# SSD.net
KiCad netlist of a schematic drawn in Altium Designer
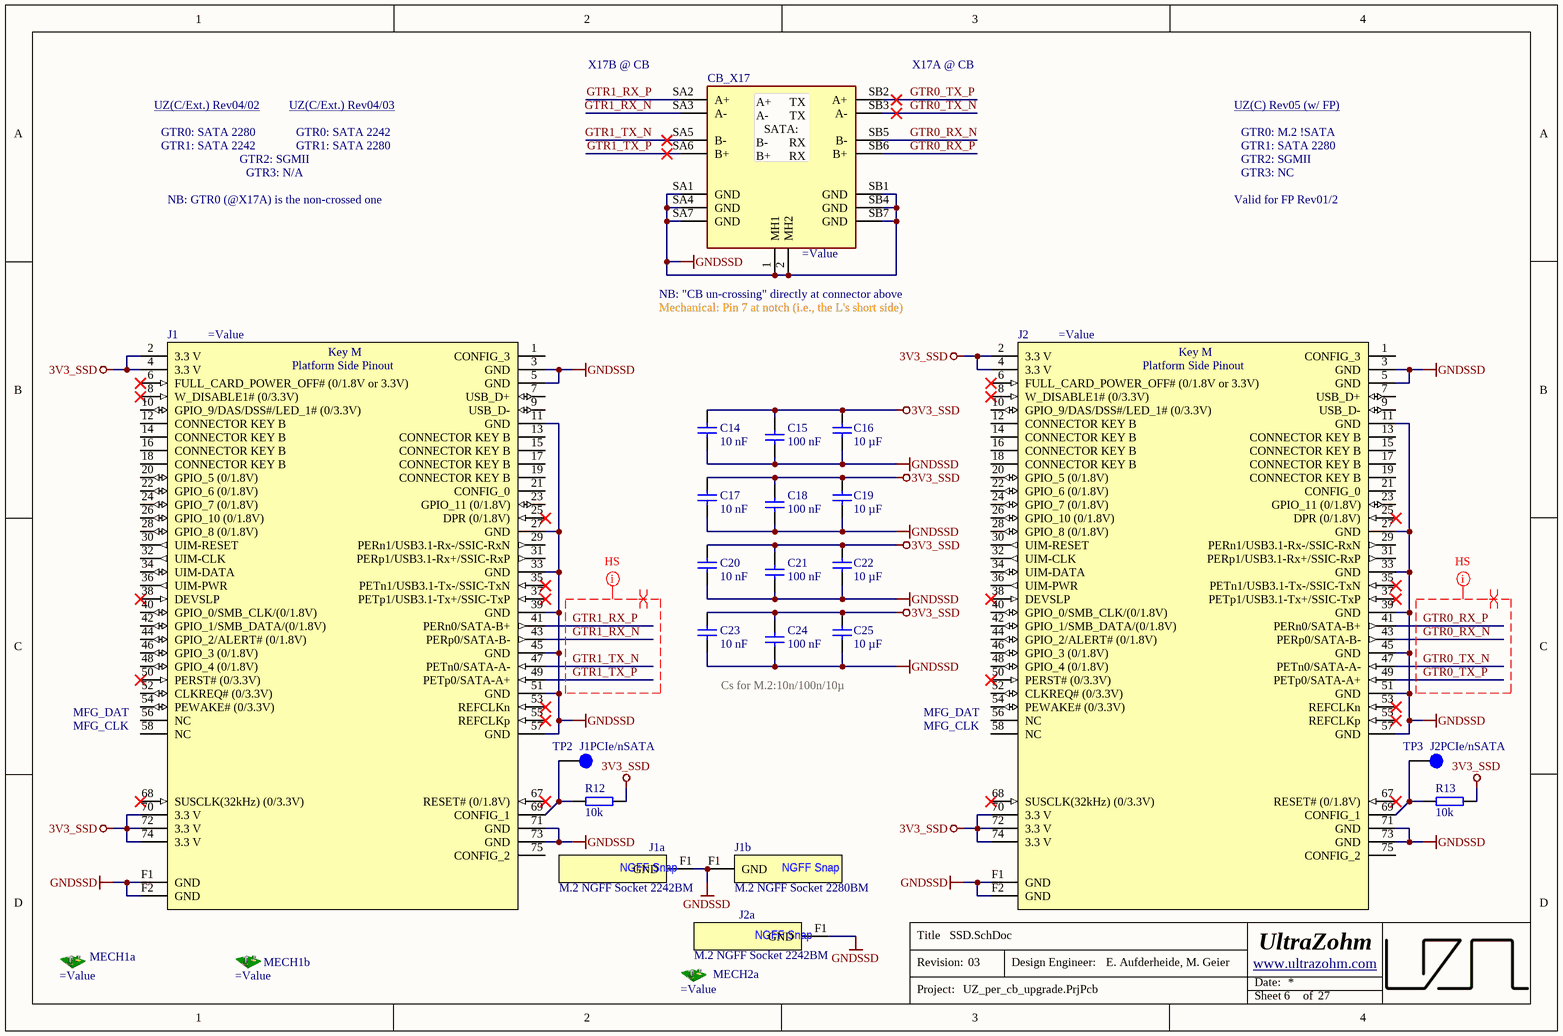
[diagram p0: SSD.SchDoc]

(export (version "E")
  (design (tool "Eeschema 10.0.6"))
  (components
    (comp (ref "C14")
      (value "10 nF")
      (footprint "C_0603_TE")
      (description "Generic capacitor")
      (fields
        (field (name "MANUFACTURER PART NUMBER") "UZgen_C_0603_10nF_50V_X7R")
        (field (name "MANUFACTURER") "UZgen")
        (field (name "CREATED FROM") "UZgenTool")
      )
      (libsource (lib "user") (part "CAP-NP"))
    )
    (comp (ref "C15")
      (value "100 nF")
      (footprint "C_0603_TE")
      (description "Generic capacitor")
      (fields
        (field (name "TOLERANCE") "10 %")
        (field (name "MANUFACTURER PART NUMBER") "UZgen_C_0603_100nF_50V_X7R")
        (field (name "CREATED FROM") "AGeiger")
      )
      (libsource (lib "user") (part "CAP-NP"))
    )
    (comp (ref "C16")
      (value "10 µF")
      (footprint "C_1206_TE")
      (description "Generic capacitor")
      (fields
        (field (name "TOLERANCE") "10 %")
        (field (name "VOLTAGE") "50V")
        (field (name "CREATED FROM") "MGeier")
      )
      (libsource (lib "user") (part "CAP-NP"))
    )
    (comp (ref "C17")
      (value "10 nF")
      (footprint "C_0603_TE")
      (description "Generic capacitor")
      (fields
        (field (name "MANUFACTURER PART NUMBER") "UZgen_C_0603_10nF_50V_X7R")
        (field (name "MANUFACTURER") "UZgen")
        (field (name "CREATED FROM") "UZgenTool")
      )
      (libsource (lib "user") (part "CAP-NP"))
    )
    (comp (ref "C18")
      (value "100 nF")
      (footprint "C_0603_TE")
      (description "Generic capacitor")
      (fields
        (field (name "TOLERANCE") "10 %")
        (field (name "MANUFACTURER PART NUMBER") "UZgen_C_0603_100nF_50V_X7R")
        (field (name "CREATED FROM") "AGeiger")
      )
      (libsource (lib "user") (part "CAP-NP"))
    )
    (comp (ref "C19")
      (value "10 µF")
      (footprint "C_1206_TE")
      (description "Generic capacitor")
      (fields
        (field (name "TOLERANCE") "10 %")
        (field (name "VOLTAGE") "50V")
        (field (name "CREATED FROM") "MGeier")
      )
      (libsource (lib "user") (part "CAP-NP"))
    )
    (comp (ref "C20")
      (value "10 nF")
      (footprint "C_0603_TE")
      (description "Generic capacitor")
      (fields
        (field (name "MANUFACTURER PART NUMBER") "UZgen_C_0603_10nF_50V_X7R")
        (field (name "MANUFACTURER") "UZgen")
        (field (name "CREATED FROM") "UZgenTool")
      )
      (libsource (lib "user") (part "CAP-NP"))
    )
    (comp (ref "C21")
      (value "100 nF")
      (footprint "C_0603_TE")
      (description "Generic capacitor")
      (fields
        (field (name "TOLERANCE") "10 %")
        (field (name "MANUFACTURER PART NUMBER") "UZgen_C_0603_100nF_50V_X7R")
        (field (name "CREATED FROM") "AGeiger")
      )
      (libsource (lib "user") (part "CAP-NP"))
    )
    (comp (ref "C22")
      (value "10 µF")
      (footprint "C_1206_TE")
      (description "Generic capacitor")
      (fields
        (field (name "TOLERANCE") "10 %")
        (field (name "VOLTAGE") "50V")
        (field (name "CREATED FROM") "MGeier")
      )
      (libsource (lib "user") (part "CAP-NP"))
    )
    (comp (ref "C23")
      (value "10 nF")
      (footprint "C_0603_TE")
      (description "Generic capacitor")
      (fields
        (field (name "MANUFACTURER PART NUMBER") "UZgen_C_0603_10nF_50V_X7R")
        (field (name "MANUFACTURER") "UZgen")
        (field (name "CREATED FROM") "UZgenTool")
      )
      (libsource (lib "user") (part "CAP-NP"))
    )
    (comp (ref "C24")
      (value "100 nF")
      (footprint "C_0603_TE")
      (description "Generic capacitor")
      (fields
        (field (name "TOLERANCE") "10 %")
        (field (name "MANUFACTURER PART NUMBER") "UZgen_C_0603_100nF_50V_X7R")
        (field (name "CREATED FROM") "AGeiger")
      )
      (libsource (lib "user") (part "CAP-NP"))
    )
    (comp (ref "C25")
      (value "10 µF")
      (footprint "C_1206_TE")
      (description "Generic capacitor")
      (fields
        (field (name "TOLERANCE") "10 %")
        (field (name "VOLTAGE") "50V")
        (field (name "CREATED FROM") "MGeier")
      )
      (libsource (lib "user") (part "CAP-NP"))
    )
    (comp (ref "CB_X17")
      (value "~")
      (footprint "XUTS-0722-2070")
      (description "1.27mm SATA Bend insert 14P -55℃~+105℃ Push-Pull,P=1.27mm Edgeboard Connectors ROHS")
      (fields
        (field (name "MANUFACTURER PART NUMBER") "XUTS-0722-2070")
        (field (name "MANUFACTURER") "Lian Xin Technology")
        (field (name "CREATED FROM") "FRosner")
      )
      (libsource (lib "user") (part "XUTS-0722-2070"))
    )
    (comp (ref "J1")
      (value "~")
      (footprint "M.2-M-Key")
      (description "M.2 0.5mm Surface Mount 67 SMD,P=0.5mm Card Edge Connectors ROHS")
      (fields
        (field (name "MANUFACTURER PART NUMBER") "1-2199230-5")
        (field (name "MANUFACTURER") "TE Connectivity")
        (field (name "CREATED FROM") "AGeiger")
      )
      (libsource (lib "user") (part "M.2 Key M"))
    )
    (comp (ref "J1a")
      (value "M.2 NGFF Socket 2242BM")
      (footprint "M.2-NGFF-Socket-2242BM")
      (description "M.2 NGFF Socket 2242BM Snap")
      (fields (field (name "MANUFACTURER") "n.a.") (field (name "CREATED FROM") "AGeiger"))
      (libsource (lib "user") (part "SNAP_M2_2242"))
    )
    (comp (ref "J1b")
      (value "M.2 NGFF Socket 2280BM")
      (footprint "M.2-NGFF-Socket-2280BM")
      (description "M.2 NGFF Socket 2280BM Snap")
      (fields (field (name "MANUFACTURER") "n.a.") (field (name "CREATED FROM") "AGeiger"))
      (libsource (lib "user") (part "SNAP_M2_2280"))
    )
    (comp (ref "J2")
      (value "~")
      (footprint "M.2-M-Key")
      (description "M.2 0.5mm Surface Mount 67 SMD,P=0.5mm Card Edge Connectors ROHS")
      (fields
        (field (name "MANUFACTURER PART NUMBER") "1-2199230-5")
        (field (name "MANUFACTURER") "TE Connectivity")
        (field (name "CREATED FROM") "AGeiger")
      )
      (libsource (lib "user") (part "M.2 Key M"))
    )
    (comp (ref "J2a")
      (value "M.2 NGFF Socket 2242BM")
      (footprint "M.2-NGFF-Socket-2242BM")
      (description "M.2 NGFF Socket 2242BM Snap")
      (fields (field (name "MANUFACTURER") "n.a.") (field (name "CREATED FROM") "AGeiger"))
      (libsource (lib "user") (part "SNAP_M2_2242"))
    )
    (comp (ref "MECH1a")
      (value "~")
      (footprint "WA-SMSI-2.5mm")
      (description "SMD Nut")
      (fields
        (field (name "LCSC PART #") "C5301784")
        (field (name "MANUFACTURER PART NUMBER") "SMTSOM325BTR")
        (field (name "CREATED FROM") "AGeiger")
      )
      (libsource (lib "user") (part "SMTSOM325BTR"))
    )
    (comp (ref "MECH1b")
      (value "~")
      (footprint "WA-SMSI-2.5mm")
      (description "SMD Nut")
      (fields
        (field (name "LCSC PART #") "C5301784")
        (field (name "MANUFACTURER PART NUMBER") "SMTSOM325BTR")
        (field (name "CREATED FROM") "AGeiger")
      )
      (libsource (lib "user") (part "SMTSOM325BTR"))
    )
    (comp (ref "MECH2a")
      (value "~")
      (footprint "WA-SMSI-2.5mm")
      (description "SMD Nut")
      (fields
        (field (name "LCSC PART #") "C5301784")
        (field (name "MANUFACTURER PART NUMBER") "SMTSOM325BTR")
        (field (name "CREATED FROM") "AGeiger")
      )
      (libsource (lib "user") (part "SMTSOM325BTR"))
    )
    (comp (ref "R12")
      (value "10k")
      (footprint "R_0603_TE")
      (description "Generic resistor")
      (fields
        (field (name "TOLERANCE") "1 %")
        (field (name "MANUFACTURER PART NUMBER") "UZgen_R_0603_10k")
        (field (name "CREATED FROM") "AGeiger")
      )
      (libsource (lib "user") (part "RES"))
    )
    (comp (ref "R13")
      (value "10k")
      (footprint "R_0603_TE")
      (description "Generic resistor")
      (fields
        (field (name "TOLERANCE") "1 %")
        (field (name "MANUFACTURER PART NUMBER") "UZgen_R_0603_10k")
        (field (name "CREATED FROM") "AGeiger")
      )
      (libsource (lib "user") (part "RES"))
    )
    (comp (ref "TP2")
      (value "J1PCIe/nSATA")
      (footprint "TP_1mm")
      (description "Testpoint 1mm")
      (fields
        (field (name "MANUFACTURER PART NUMBER") "NULL")
        (field (name "CREATED") "2018_06_25_AGeiger")
        (field (name "CREATED FROM") "AGeiger")
      )
      (libsource (lib "user") (part "TP_1mm"))
    )
    (comp (ref "TP3")
      (value "J2PCIe/nSATA")
      (footprint "TP_1mm")
      (description "Testpoint 1mm")
      (fields
        (field (name "MANUFACTURER PART NUMBER") "NULL")
        (field (name "CREATED") "2018_06_25_AGeiger")
        (field (name "CREATED FROM") "AGeiger")
      )
      (libsource (lib "user") (part "TP_1mm"))
    )
  )
  (nets
    (net (code "1") (name "/GTR0_RX_N") (class "Default")
      (node (ref "CB_X17") (pin "SB5") (pinfunction "B-_SB5") (pintype "passive"))
      (node (ref "J2") (pin "43") (pinfunction "PERp0/SATA-B-_43") (pintype "output"))
    )
    (net (code "2") (name "/GTR0_RX_P") (class "Default")
      (node (ref "CB_X17") (pin "SB6") (pinfunction "B+_SB6") (pintype "passive"))
      (node (ref "J2") (pin "41") (pinfunction "PERn0/SATA-B+_41") (pintype "output"))
    )
    (net (code "3") (name "/GTR0_TX_N") (class "Default")
      (node (ref "CB_X17") (pin "SB3") (pinfunction "A-_SB3") (pintype "passive"))
      (node (ref "J2") (pin "47") (pinfunction "PETn0/SATA-A-_47") (pintype "input"))
    )
    (net (code "4") (name "/GTR0_TX_P") (class "Default")
      (node (ref "CB_X17") (pin "SB2") (pinfunction "A+_SB2") (pintype "passive"))
      (node (ref "J2") (pin "49") (pinfunction "PETp0/SATA-A+_49") (pintype "input"))
    )
    (net (code "5") (name "/GTR1_RX_N") (class "Default")
      (node (ref "CB_X17") (pin "SA3") (pinfunction "A-_SA3") (pintype "passive"))
      (node (ref "J1") (pin "43") (pinfunction "PERp0/SATA-B-_43") (pintype "output"))
    )
    (net (code "6") (name "/GTR1_RX_P") (class "Default")
      (node (ref "CB_X17") (pin "SA2") (pinfunction "A+_SA2") (pintype "passive"))
      (node (ref "J1") (pin "41") (pinfunction "PERn0/SATA-B+_41") (pintype "output"))
    )
    (net (code "7") (name "/GTR1_TX_N") (class "Default")
      (node (ref "CB_X17") (pin "SA5") (pinfunction "B-_SA5") (pintype "passive"))
      (node (ref "J1") (pin "47") (pinfunction "PETn0/SATA-A-_47") (pintype "input"))
    )
    (net (code "8") (name "/GTR1_TX_P") (class "Default")
      (node (ref "CB_X17") (pin "SA6") (pinfunction "B+_SA6") (pintype "passive"))
      (node (ref "J1") (pin "49") (pinfunction "PETp0/SATA-A+_49") (pintype "input"))
    )
    (net (code "9") (name "3V3_SSD") (class "Default")
      (node (ref "C14") (pin "1") (pinfunction "1_1") (pintype "passive"))
      (node (ref "C15") (pin "1") (pinfunction "1_1") (pintype "passive"))
      (node (ref "C16") (pin "2") (pinfunction "2_2") (pintype "passive"))
      (node (ref "C17") (pin "1") (pinfunction "1_1") (pintype "passive"))
      (node (ref "C18") (pin "1") (pinfunction "1_1") (pintype "passive"))
      (node (ref "C19") (pin "2") (pinfunction "2_2") (pintype "passive"))
      (node (ref "C20") (pin "1") (pinfunction "1_1") (pintype "passive"))
      (node (ref "C21") (pin "1") (pinfunction "1_1") (pintype "passive"))
      (node (ref "C22") (pin "2") (pinfunction "2_2") (pintype "passive"))
      (node (ref "C23") (pin "1") (pinfunction "1_1") (pintype "passive"))
      (node (ref "C24") (pin "1") (pinfunction "1_1") (pintype "passive"))
      (node (ref "C25") (pin "2") (pinfunction "2_2") (pintype "passive"))
      (node (ref "J1") (pin "2") (pinfunction "3.3_V_2") (pintype "power_in"))
      (node (ref "J1") (pin "4") (pinfunction "3.3_V_4") (pintype "power_in"))
      (node (ref "J1") (pin "70") (pinfunction "3.3_V_70") (pintype "power_in"))
      (node (ref "J1") (pin "72") (pinfunction "3.3_V_72") (pintype "power_in"))
      (node (ref "J1") (pin "74") (pinfunction "3.3_V_74") (pintype "power_in"))
      (node (ref "J2") (pin "2") (pinfunction "3.3_V_2") (pintype "power_in"))
      (node (ref "J2") (pin "4") (pinfunction "3.3_V_4") (pintype "power_in"))
      (node (ref "J2") (pin "70") (pinfunction "3.3_V_70") (pintype "power_in"))
      (node (ref "J2") (pin "72") (pinfunction "3.3_V_72") (pintype "power_in"))
      (node (ref "J2") (pin "74") (pinfunction "3.3_V_74") (pintype "power_in"))
      (node (ref "R12") (pin "1") (pinfunction "1_1") (pintype "passive"))
      (node (ref "R13") (pin "1") (pinfunction "1_1") (pintype "passive"))
    )
    (net (code "10") (name "GNDSSD") (class "Default")
      (node (ref "C14") (pin "2") (pinfunction "2_2") (pintype "passive"))
      (node (ref "C15") (pin "2") (pinfunction "2_2") (pintype "passive"))
      (node (ref "C16") (pin "1") (pinfunction "1_1") (pintype "passive"))
      (node (ref "C17") (pin "2") (pinfunction "2_2") (pintype "passive"))
      (node (ref "C18") (pin "2") (pinfunction "2_2") (pintype "passive"))
      (node (ref "C19") (pin "1") (pinfunction "1_1") (pintype "passive"))
      (node (ref "C20") (pin "2") (pinfunction "2_2") (pintype "passive"))
      (node (ref "C21") (pin "2") (pinfunction "2_2") (pintype "passive"))
      (node (ref "C22") (pin "1") (pinfunction "1_1") (pintype "passive"))
      (node (ref "C23") (pin "2") (pinfunction "2_2") (pintype "passive"))
      (node (ref "C24") (pin "2") (pinfunction "2_2") (pintype "passive"))
      (node (ref "C25") (pin "1") (pinfunction "1_1") (pintype "passive"))
      (node (ref "CB_X17") (pin "1") (pinfunction "MH1_1") (pintype "passive"))
      (node (ref "CB_X17") (pin "2") (pinfunction "MH2_2") (pintype "passive"))
      (node (ref "CB_X17") (pin "SA1") (pinfunction "GND_SA1") (pintype "passive"))
      (node (ref "CB_X17") (pin "SA4") (pinfunction "GND_SA4") (pintype "passive"))
      (node (ref "CB_X17") (pin "SA7") (pinfunction "GND_SA7") (pintype "passive"))
      (node (ref "CB_X17") (pin "SB1") (pinfunction "GND_SB1") (pintype "passive"))
      (node (ref "CB_X17") (pin "SB4") (pinfunction "GND_SB4") (pintype "passive"))
      (node (ref "CB_X17") (pin "SB7") (pinfunction "GND_SB7") (pintype "passive"))
      (node (ref "J1") (pin "11") (pinfunction "GND_11") (pintype "power_in"))
      (node (ref "J1") (pin "27") (pinfunction "GND_27") (pintype "power_in"))
      (node (ref "J1") (pin "3") (pinfunction "GND_3") (pintype "power_in"))
      (node (ref "J1") (pin "33") (pinfunction "GND_33") (pintype "power_in"))
      (node (ref "J1") (pin "39") (pinfunction "GND_39") (pintype "power_in"))
      (node (ref "J1") (pin "45") (pinfunction "GND_45") (pintype "power_in"))
      (node (ref "J1") (pin "5") (pinfunction "GND_5") (pintype "power_in"))
      (node (ref "J1") (pin "51") (pinfunction "GND_51") (pintype "power_in"))
      (node (ref "J1") (pin "57") (pinfunction "GND_57") (pintype "power_in"))
      (node (ref "J1") (pin "71") (pinfunction "GND_71") (pintype "power_in"))
      (node (ref "J1") (pin "73") (pinfunction "GND_73") (pintype "power_in"))
      (node (ref "J1") (pin "F1") (pinfunction "GND_F1") (pintype "power_in"))
      (node (ref "J1") (pin "F2") (pinfunction "GND_F2") (pintype "power_in"))
      (node (ref "J1a") (pin "F1") (pinfunction "GND_F1") (pintype "passive"))
      (node (ref "J1b") (pin "F1") (pinfunction "GND_F1") (pintype "passive"))
      (node (ref "J2") (pin "11") (pinfunction "GND_11") (pintype "power_in"))
      (node (ref "J2") (pin "27") (pinfunction "GND_27") (pintype "power_in"))
      (node (ref "J2") (pin "3") (pinfunction "GND_3") (pintype "power_in"))
      (node (ref "J2") (pin "33") (pinfunction "GND_33") (pintype "power_in"))
      (node (ref "J2") (pin "39") (pinfunction "GND_39") (pintype "power_in"))
      (node (ref "J2") (pin "45") (pinfunction "GND_45") (pintype "power_in"))
      (node (ref "J2") (pin "5") (pinfunction "GND_5") (pintype "power_in"))
      (node (ref "J2") (pin "51") (pinfunction "GND_51") (pintype "power_in"))
      (node (ref "J2") (pin "57") (pinfunction "GND_57") (pintype "power_in"))
      (node (ref "J2") (pin "71") (pinfunction "GND_71") (pintype "power_in"))
      (node (ref "J2") (pin "73") (pinfunction "GND_73") (pintype "power_in"))
      (node (ref "J2") (pin "F1") (pinfunction "GND_F1") (pintype "power_in"))
      (node (ref "J2") (pin "F2") (pinfunction "GND_F2") (pintype "power_in"))
      (node (ref "J2a") (pin "F1") (pinfunction "GND_F1") (pintype "passive"))
    )
    (net (code "11") (name "Net-(J1-CONFIG_1)") (class "Default")
      (node (ref "J1") (pin "69") (pinfunction "CONFIG_1_69") (pintype "passive"))
      (node (ref "R12") (pin "2") (pinfunction "2_2") (pintype "passive"))
      (node (ref "TP2") (pin "1") (pintype "passive"))
    )
    (net (code "12") (name "Net-(J2-CONFIG_1)") (class "Default")
      (node (ref "J2") (pin "69") (pinfunction "CONFIG_1_69") (pintype "passive"))
      (node (ref "R13") (pin "2") (pinfunction "2_2") (pintype "passive"))
      (node (ref "TP3") (pin "1") (pintype "passive"))
    )
    (net (code "13") (name "unconnected-(J1-CLKREQ#_(0{slash}3.3V)-Pad52)") (class "Default")
      (node (ref "J1") (pin "52") (pinfunction "CLKREQ#_(0/3.3V)_52") (pintype "bidirectional"))
    )
    (net (code "14") (name "unconnected-(J1-CONFIG_0-Pad21)") (class "Default")
      (node (ref "J1") (pin "21") (pinfunction "CONFIG_0_21") (pintype "passive"))
    )
    (net (code "15") (name "unconnected-(J1-CONFIG_2-Pad75)") (class "Default")
      (node (ref "J1") (pin "75") (pinfunction "CONFIG_2_75") (pintype "passive"))
    )
    (net (code "16") (name "unconnected-(J1-CONFIG_3-Pad1)") (class "Default")
      (node (ref "J1") (pin "1") (pinfunction "CONFIG_3_1") (pintype "passive"))
    )
    (net (code "17") (name "unconnected-(J1-CONNECTOR_KEY_B-Pad12)") (class "Default")
      (node (ref "J1") (pin "12") (pinfunction "CONNECTOR_KEY_B_12") (pintype "passive"))
    )
    (net (code "18") (name "unconnected-(J1-CONNECTOR_KEY_B-Pad13)") (class "Default")
      (node (ref "J1") (pin "13") (pinfunction "CONNECTOR_KEY_B_13") (pintype "passive"))
    )
    (net (code "19") (name "unconnected-(J1-CONNECTOR_KEY_B-Pad14)") (class "Default")
      (node (ref "J1") (pin "14") (pinfunction "CONNECTOR_KEY_B_14") (pintype "passive"))
    )
    (net (code "20") (name "unconnected-(J1-CONNECTOR_KEY_B-Pad15)") (class "Default")
      (node (ref "J1") (pin "15") (pinfunction "CONNECTOR_KEY_B_15") (pintype "passive"))
    )
    (net (code "21") (name "unconnected-(J1-CONNECTOR_KEY_B-Pad16)") (class "Default")
      (node (ref "J1") (pin "16") (pinfunction "CONNECTOR_KEY_B_16") (pintype "passive"))
    )
    (net (code "22") (name "unconnected-(J1-CONNECTOR_KEY_B-Pad17)") (class "Default")
      (node (ref "J1") (pin "17") (pinfunction "CONNECTOR_KEY_B_17") (pintype "passive"))
    )
    (net (code "23") (name "unconnected-(J1-CONNECTOR_KEY_B-Pad18)") (class "Default")
      (node (ref "J1") (pin "18") (pinfunction "CONNECTOR_KEY_B_18") (pintype "passive"))
    )
    (net (code "24") (name "unconnected-(J1-CONNECTOR_KEY_B-Pad19)") (class "Default")
      (node (ref "J1") (pin "19") (pinfunction "CONNECTOR_KEY_B_19") (pintype "passive"))
    )
    (net (code "25") (name "unconnected-(J1-DEVSLP-Pad38)") (class "Default")
      (node (ref "J1") (pin "38") (pinfunction "DEVSLP_38") (pintype "input+no_connect"))
    )
    (net (code "26") (name "unconnected-(J1-DPR_(0{slash}1.8V)-Pad25)") (class "Default")
      (node (ref "J1") (pin "25") (pinfunction "DPR_(0/1.8V)_25") (pintype "input+no_connect"))
    )
    (net (code "27") (name "unconnected-(J1-FULL_CARD_POWER_OFF#_(0{slash}1.8V_or_3.3V)-Pad6)") (class "Default")
      (node (ref "J1") (pin "6") (pinfunction "FULL_CARD_POWER_OFF#_(0/1.8V_or_3.3V)_6") (pintype "input+no_connect"))
    )
    (net (code "28") (name "unconnected-(J1-GPIO_0{slash}SMB_CLK{slash}(0{slash}1.8V)-Pad40)") (class "Default")
      (node (ref "J1") (pin "40") (pinfunction "GPIO_0/SMB_CLK/(0/1.8V)_40") (pintype "bidirectional"))
    )
    (net (code "29") (name "unconnected-(J1-GPIO_1{slash}SMB_DATA{slash}(0{slash}1.8V)-Pad42)") (class "Default")
      (node (ref "J1") (pin "42") (pinfunction "GPIO_1/SMB_DATA/(0/1.8V)_42") (pintype "bidirectional"))
    )
    (net (code "30") (name "unconnected-(J1-GPIO_2{slash}ALERT#_(0{slash}1.8V)-Pad44)") (class "Default")
      (node (ref "J1") (pin "44") (pinfunction "GPIO_2/ALERT#_(0/1.8V)_44") (pintype "bidirectional"))
    )
    (net (code "31") (name "unconnected-(J1-GPIO_3_(0{slash}1.8V)-Pad46)") (class "Default")
      (node (ref "J1") (pin "46") (pinfunction "GPIO_3_(0/1.8V)_46") (pintype "bidirectional"))
    )
    (net (code "32") (name "unconnected-(J1-GPIO_4_(0{slash}1.8V)-Pad48)") (class "Default")
      (node (ref "J1") (pin "48") (pinfunction "GPIO_4_(0/1.8V)_48") (pintype "bidirectional"))
    )
    (net (code "33") (name "unconnected-(J1-GPIO_5_(0{slash}1.8V)-Pad20)") (class "Default")
      (node (ref "J1") (pin "20") (pinfunction "GPIO_5_(0/1.8V)_20") (pintype "bidirectional"))
    )
    (net (code "34") (name "unconnected-(J1-GPIO_6_(0{slash}1.8V)-Pad22)") (class "Default")
      (node (ref "J1") (pin "22") (pinfunction "GPIO_6_(0/1.8V)_22") (pintype "bidirectional"))
    )
    (net (code "35") (name "unconnected-(J1-GPIO_7_(0{slash}1.8V)-Pad24)") (class "Default")
      (node (ref "J1") (pin "24") (pinfunction "GPIO_7_(0/1.8V)_24") (pintype "bidirectional"))
    )
    (net (code "36") (name "unconnected-(J1-GPIO_8_(0{slash}1.8V)-Pad28)") (class "Default")
      (node (ref "J1") (pin "28") (pinfunction "GPIO_8_(0/1.8V)_28") (pintype "bidirectional"))
    )
    (net (code "37") (name "unconnected-(J1-GPIO_9{slash}DAS{slash}DSS#{slash}LED_1#_(0{slash}3.3V)-Pad10)") (class "Default")
      (node (ref "J1") (pin "10") (pinfunction "GPIO_9/DAS/DSS#/LED_1#_(0/3.3V)_10") (pintype "bidirectional"))
    )
    (net (code "38") (name "unconnected-(J1-GPIO_10_(0{slash}1.8V)-Pad26)") (class "Default")
      (node (ref "J1") (pin "26") (pinfunction "GPIO_10_(0/1.8V)_26") (pintype "bidirectional"))
    )
    (net (code "39") (name "unconnected-(J1-GPIO_11_(0{slash}1.8V)-Pad23)") (class "Default")
      (node (ref "J1") (pin "23") (pinfunction "GPIO_11_(0/1.8V)_23") (pintype "bidirectional"))
    )
    (net (code "40") (name "unconnected-(J1-NC-Pad56)") (class "Default")
      (node (ref "J1") (pin "56") (pinfunction "NC_56") (pintype "passive"))
    )
    (net (code "41") (name "unconnected-(J1-NC-Pad58)") (class "Default")
      (node (ref "J1") (pin "58") (pinfunction "NC_58") (pintype "passive"))
    )
    (net (code "42") (name "unconnected-(J1-PERST#_(0{slash}3.3V)-Pad50)") (class "Default")
      (node (ref "J1") (pin "50") (pinfunction "PERST#_(0/3.3V)_50") (pintype "input+no_connect"))
    )
    (net (code "43") (name "unconnected-(J1-PERn1{slash}USB3.1-Rx-{slash}SSIC-RxN-Pad29)") (class "Default")
      (node (ref "J1") (pin "29") (pinfunction "PERn1/USB3.1-Rx-/SSIC-RxN_29") (pintype "output"))
    )
    (net (code "44") (name "unconnected-(J1-PERp1{slash}USB3.1-Rx+{slash}SSIC-RxP-Pad31)") (class "Default")
      (node (ref "J1") (pin "31") (pinfunction "PERp1/USB3.1-Rx+/SSIC-RxP_31") (pintype "output"))
    )
    (net (code "45") (name "unconnected-(J1-PETn1{slash}USB3.1-Tx-{slash}SSIC-TxN-Pad35)") (class "Default")
      (node (ref "J1") (pin "35") (pinfunction "PETn1/USB3.1-Tx-/SSIC-TxN_35") (pintype "input+no_connect"))
    )
    (net (code "46") (name "unconnected-(J1-PETp1{slash}USB3.1-Tx+{slash}SSIC-TxP-Pad37)") (class "Default")
      (node (ref "J1") (pin "37") (pinfunction "PETp1/USB3.1-Tx+/SSIC-TxP_37") (pintype "input+no_connect"))
    )
    (net (code "47") (name "unconnected-(J1-PEWAKE#_(0{slash}3.3V)-Pad54)") (class "Default")
      (node (ref "J1") (pin "54") (pinfunction "PEWAKE#_(0/3.3V)_54") (pintype "bidirectional"))
    )
    (net (code "48") (name "unconnected-(J1-REFCLKn-Pad53)") (class "Default")
      (node (ref "J1") (pin "53") (pinfunction "REFCLKn_53") (pintype "input+no_connect"))
    )
    (net (code "49") (name "unconnected-(J1-REFCLKp-Pad55)") (class "Default")
      (node (ref "J1") (pin "55") (pinfunction "REFCLKp_55") (pintype "input+no_connect"))
    )
    (net (code "50") (name "unconnected-(J1-RESET#_(0{slash}1.8V)-Pad67)") (class "Default")
      (node (ref "J1") (pin "67") (pinfunction "RESET#_(0/1.8V)_67") (pintype "input+no_connect"))
    )
    (net (code "51") (name "unconnected-(J1-SUSCLK(32kHz)_(0{slash}3.3V)-Pad68)") (class "Default")
      (node (ref "J1") (pin "68") (pinfunction "SUSCLK(32kHz)_(0/3.3V)_68") (pintype "input+no_connect"))
    )
    (net (code "52") (name "unconnected-(J1-UIM-CLK-Pad32)") (class "Default")
      (node (ref "J1") (pin "32") (pinfunction "UIM-CLK_32") (pintype "output"))
    )
    (net (code "53") (name "unconnected-(J1-UIM-DATA-Pad34)") (class "Default")
      (node (ref "J1") (pin "34") (pinfunction "UIM-DATA_34") (pintype "bidirectional"))
    )
    (net (code "54") (name "unconnected-(J1-UIM-PWR-Pad36)") (class "Default")
      (node (ref "J1") (pin "36") (pinfunction "UIM-PWR_36") (pintype "output"))
    )
    (net (code "55") (name "unconnected-(J1-UIM-RESET-Pad30)") (class "Default")
      (node (ref "J1") (pin "30") (pinfunction "UIM-RESET_30") (pintype "output"))
    )
    (net (code "56") (name "unconnected-(J1-USB_D+-Pad7)") (class "Default")
      (node (ref "J1") (pin "7") (pinfunction "USB_D+_7") (pintype "bidirectional"))
    )
    (net (code "57") (name "unconnected-(J1-USB_D--Pad9)") (class "Default")
      (node (ref "J1") (pin "9") (pinfunction "USB_D-_9") (pintype "bidirectional"))
    )
    (net (code "58") (name "unconnected-(J1-W_DISABLE1#_(0{slash}3.3V)-Pad8)") (class "Default")
      (node (ref "J1") (pin "8") (pinfunction "W_DISABLE1#_(0/3.3V)_8") (pintype "input+no_connect"))
    )
    (net (code "59") (name "unconnected-(J2-CLKREQ#_(0{slash}3.3V)-Pad52)") (class "Default")
      (node (ref "J2") (pin "52") (pinfunction "CLKREQ#_(0/3.3V)_52") (pintype "bidirectional"))
    )
    (net (code "60") (name "unconnected-(J2-CONFIG_0-Pad21)") (class "Default")
      (node (ref "J2") (pin "21") (pinfunction "CONFIG_0_21") (pintype "passive"))
    )
    (net (code "61") (name "unconnected-(J2-CONFIG_2-Pad75)") (class "Default")
      (node (ref "J2") (pin "75") (pinfunction "CONFIG_2_75") (pintype "passive"))
    )
    (net (code "62") (name "unconnected-(J2-CONFIG_3-Pad1)") (class "Default")
      (node (ref "J2") (pin "1") (pinfunction "CONFIG_3_1") (pintype "passive"))
    )
    (net (code "63") (name "unconnected-(J2-CONNECTOR_KEY_B-Pad12)") (class "Default")
      (node (ref "J2") (pin "12") (pinfunction "CONNECTOR_KEY_B_12") (pintype "passive"))
    )
    (net (code "64") (name "unconnected-(J2-CONNECTOR_KEY_B-Pad13)") (class "Default")
      (node (ref "J2") (pin "13") (pinfunction "CONNECTOR_KEY_B_13") (pintype "passive"))
    )
    (net (code "65") (name "unconnected-(J2-CONNECTOR_KEY_B-Pad14)") (class "Default")
      (node (ref "J2") (pin "14") (pinfunction "CONNECTOR_KEY_B_14") (pintype "passive"))
    )
    (net (code "66") (name "unconnected-(J2-CONNECTOR_KEY_B-Pad15)") (class "Default")
      (node (ref "J2") (pin "15") (pinfunction "CONNECTOR_KEY_B_15") (pintype "passive"))
    )
    (net (code "67") (name "unconnected-(J2-CONNECTOR_KEY_B-Pad16)") (class "Default")
      (node (ref "J2") (pin "16") (pinfunction "CONNECTOR_KEY_B_16") (pintype "passive"))
    )
    (net (code "68") (name "unconnected-(J2-CONNECTOR_KEY_B-Pad17)") (class "Default")
      (node (ref "J2") (pin "17") (pinfunction "CONNECTOR_KEY_B_17") (pintype "passive"))
    )
    (net (code "69") (name "unconnected-(J2-CONNECTOR_KEY_B-Pad18)") (class "Default")
      (node (ref "J2") (pin "18") (pinfunction "CONNECTOR_KEY_B_18") (pintype "passive"))
    )
    (net (code "70") (name "unconnected-(J2-CONNECTOR_KEY_B-Pad19)") (class "Default")
      (node (ref "J2") (pin "19") (pinfunction "CONNECTOR_KEY_B_19") (pintype "passive"))
    )
    (net (code "71") (name "unconnected-(J2-DEVSLP-Pad38)") (class "Default")
      (node (ref "J2") (pin "38") (pinfunction "DEVSLP_38") (pintype "input+no_connect"))
    )
    (net (code "72") (name "unconnected-(J2-DPR_(0{slash}1.8V)-Pad25)") (class "Default")
      (node (ref "J2") (pin "25") (pinfunction "DPR_(0/1.8V)_25") (pintype "input+no_connect"))
    )
    (net (code "73") (name "unconnected-(J2-FULL_CARD_POWER_OFF#_(0{slash}1.8V_or_3.3V)-Pad6)") (class "Default")
      (node (ref "J2") (pin "6") (pinfunction "FULL_CARD_POWER_OFF#_(0/1.8V_or_3.3V)_6") (pintype "input+no_connect"))
    )
    (net (code "74") (name "unconnected-(J2-GPIO_0{slash}SMB_CLK{slash}(0{slash}1.8V)-Pad40)") (class "Default")
      (node (ref "J2") (pin "40") (pinfunction "GPIO_0/SMB_CLK/(0/1.8V)_40") (pintype "bidirectional"))
    )
    (net (code "75") (name "unconnected-(J2-GPIO_1{slash}SMB_DATA{slash}(0{slash}1.8V)-Pad42)") (class "Default")
      (node (ref "J2") (pin "42") (pinfunction "GPIO_1/SMB_DATA/(0/1.8V)_42") (pintype "bidirectional"))
    )
    (net (code "76") (name "unconnected-(J2-GPIO_2{slash}ALERT#_(0{slash}1.8V)-Pad44)") (class "Default")
      (node (ref "J2") (pin "44") (pinfunction "GPIO_2/ALERT#_(0/1.8V)_44") (pintype "bidirectional"))
    )
    (net (code "77") (name "unconnected-(J2-GPIO_3_(0{slash}1.8V)-Pad46)") (class "Default")
      (node (ref "J2") (pin "46") (pinfunction "GPIO_3_(0/1.8V)_46") (pintype "bidirectional"))
    )
    (net (code "78") (name "unconnected-(J2-GPIO_4_(0{slash}1.8V)-Pad48)") (class "Default")
      (node (ref "J2") (pin "48") (pinfunction "GPIO_4_(0/1.8V)_48") (pintype "bidirectional"))
    )
    (net (code "79") (name "unconnected-(J2-GPIO_5_(0{slash}1.8V)-Pad20)") (class "Default")
      (node (ref "J2") (pin "20") (pinfunction "GPIO_5_(0/1.8V)_20") (pintype "bidirectional"))
    )
    (net (code "80") (name "unconnected-(J2-GPIO_6_(0{slash}1.8V)-Pad22)") (class "Default")
      (node (ref "J2") (pin "22") (pinfunction "GPIO_6_(0/1.8V)_22") (pintype "bidirectional"))
    )
    (net (code "81") (name "unconnected-(J2-GPIO_7_(0{slash}1.8V)-Pad24)") (class "Default")
      (node (ref "J2") (pin "24") (pinfunction "GPIO_7_(0/1.8V)_24") (pintype "bidirectional"))
    )
    (net (code "82") (name "unconnected-(J2-GPIO_8_(0{slash}1.8V)-Pad28)") (class "Default")
      (node (ref "J2") (pin "28") (pinfunction "GPIO_8_(0/1.8V)_28") (pintype "bidirectional"))
    )
    (net (code "83") (name "unconnected-(J2-GPIO_9{slash}DAS{slash}DSS#{slash}LED_1#_(0{slash}3.3V)-Pad10)") (class "Default")
      (node (ref "J2") (pin "10") (pinfunction "GPIO_9/DAS/DSS#/LED_1#_(0/3.3V)_10") (pintype "bidirectional"))
    )
    (net (code "84") (name "unconnected-(J2-GPIO_10_(0{slash}1.8V)-Pad26)") (class "Default")
      (node (ref "J2") (pin "26") (pinfunction "GPIO_10_(0/1.8V)_26") (pintype "bidirectional"))
    )
    (net (code "85") (name "unconnected-(J2-GPIO_11_(0{slash}1.8V)-Pad23)") (class "Default")
      (node (ref "J2") (pin "23") (pinfunction "GPIO_11_(0/1.8V)_23") (pintype "bidirectional"))
    )
    (net (code "86") (name "unconnected-(J2-NC-Pad56)") (class "Default")
      (node (ref "J2") (pin "56") (pinfunction "NC_56") (pintype "passive"))
    )
    (net (code "87") (name "unconnected-(J2-NC-Pad58)") (class "Default")
      (node (ref "J2") (pin "58") (pinfunction "NC_58") (pintype "passive"))
    )
    (net (code "88") (name "unconnected-(J2-PERST#_(0{slash}3.3V)-Pad50)") (class "Default")
      (node (ref "J2") (pin "50") (pinfunction "PERST#_(0/3.3V)_50") (pintype "input+no_connect"))
    )
    (net (code "89") (name "unconnected-(J2-PERn1{slash}USB3.1-Rx-{slash}SSIC-RxN-Pad29)") (class "Default")
      (node (ref "J2") (pin "29") (pinfunction "PERn1/USB3.1-Rx-/SSIC-RxN_29") (pintype "output"))
    )
    (net (code "90") (name "unconnected-(J2-PERp1{slash}USB3.1-Rx+{slash}SSIC-RxP-Pad31)") (class "Default")
      (node (ref "J2") (pin "31") (pinfunction "PERp1/USB3.1-Rx+/SSIC-RxP_31") (pintype "output"))
    )
    (net (code "91") (name "unconnected-(J2-PETn1{slash}USB3.1-Tx-{slash}SSIC-TxN-Pad35)") (class "Default")
      (node (ref "J2") (pin "35") (pinfunction "PETn1/USB3.1-Tx-/SSIC-TxN_35") (pintype "input+no_connect"))
    )
    (net (code "92") (name "unconnected-(J2-PETp1{slash}USB3.1-Tx+{slash}SSIC-TxP-Pad37)") (class "Default")
      (node (ref "J2") (pin "37") (pinfunction "PETp1/USB3.1-Tx+/SSIC-TxP_37") (pintype "input+no_connect"))
    )
    (net (code "93") (name "unconnected-(J2-PEWAKE#_(0{slash}3.3V)-Pad54)") (class "Default")
      (node (ref "J2") (pin "54") (pinfunction "PEWAKE#_(0/3.3V)_54") (pintype "bidirectional"))
    )
    (net (code "94") (name "unconnected-(J2-REFCLKn-Pad53)") (class "Default")
      (node (ref "J2") (pin "53") (pinfunction "REFCLKn_53") (pintype "input+no_connect"))
    )
    (net (code "95") (name "unconnected-(J2-REFCLKp-Pad55)") (class "Default")
      (node (ref "J2") (pin "55") (pinfunction "REFCLKp_55") (pintype "input+no_connect"))
    )
    (net (code "96") (name "unconnected-(J2-RESET#_(0{slash}1.8V)-Pad67)") (class "Default")
      (node (ref "J2") (pin "67") (pinfunction "RESET#_(0/1.8V)_67") (pintype "input+no_connect"))
    )
    (net (code "97") (name "unconnected-(J2-SUSCLK(32kHz)_(0{slash}3.3V)-Pad68)") (class "Default")
      (node (ref "J2") (pin "68") (pinfunction "SUSCLK(32kHz)_(0/3.3V)_68") (pintype "input+no_connect"))
    )
    (net (code "98") (name "unconnected-(J2-UIM-CLK-Pad32)") (class "Default")
      (node (ref "J2") (pin "32") (pinfunction "UIM-CLK_32") (pintype "output"))
    )
    (net (code "99") (name "unconnected-(J2-UIM-DATA-Pad34)") (class "Default")
      (node (ref "J2") (pin "34") (pinfunction "UIM-DATA_34") (pintype "bidirectional"))
    )
    (net (code "100") (name "unconnected-(J2-UIM-PWR-Pad36)") (class "Default")
      (node (ref "J2") (pin "36") (pinfunction "UIM-PWR_36") (pintype "output"))
    )
    (net (code "101") (name "unconnected-(J2-UIM-RESET-Pad30)") (class "Default")
      (node (ref "J2") (pin "30") (pinfunction "UIM-RESET_30") (pintype "output"))
    )
    (net (code "102") (name "unconnected-(J2-USB_D+-Pad7)") (class "Default")
      (node (ref "J2") (pin "7") (pinfunction "USB_D+_7") (pintype "bidirectional"))
    )
    (net (code "103") (name "unconnected-(J2-USB_D--Pad9)") (class "Default")
      (node (ref "J2") (pin "9") (pinfunction "USB_D-_9") (pintype "bidirectional"))
    )
    (net (code "104") (name "unconnected-(J2-W_DISABLE1#_(0{slash}3.3V)-Pad8)") (class "Default")
      (node (ref "J2") (pin "8") (pinfunction "W_DISABLE1#_(0/3.3V)_8") (pintype "input+no_connect"))
    )
  )
)
